# durtest3.net
KiCad netlist of a schematic drawn in EAGLE
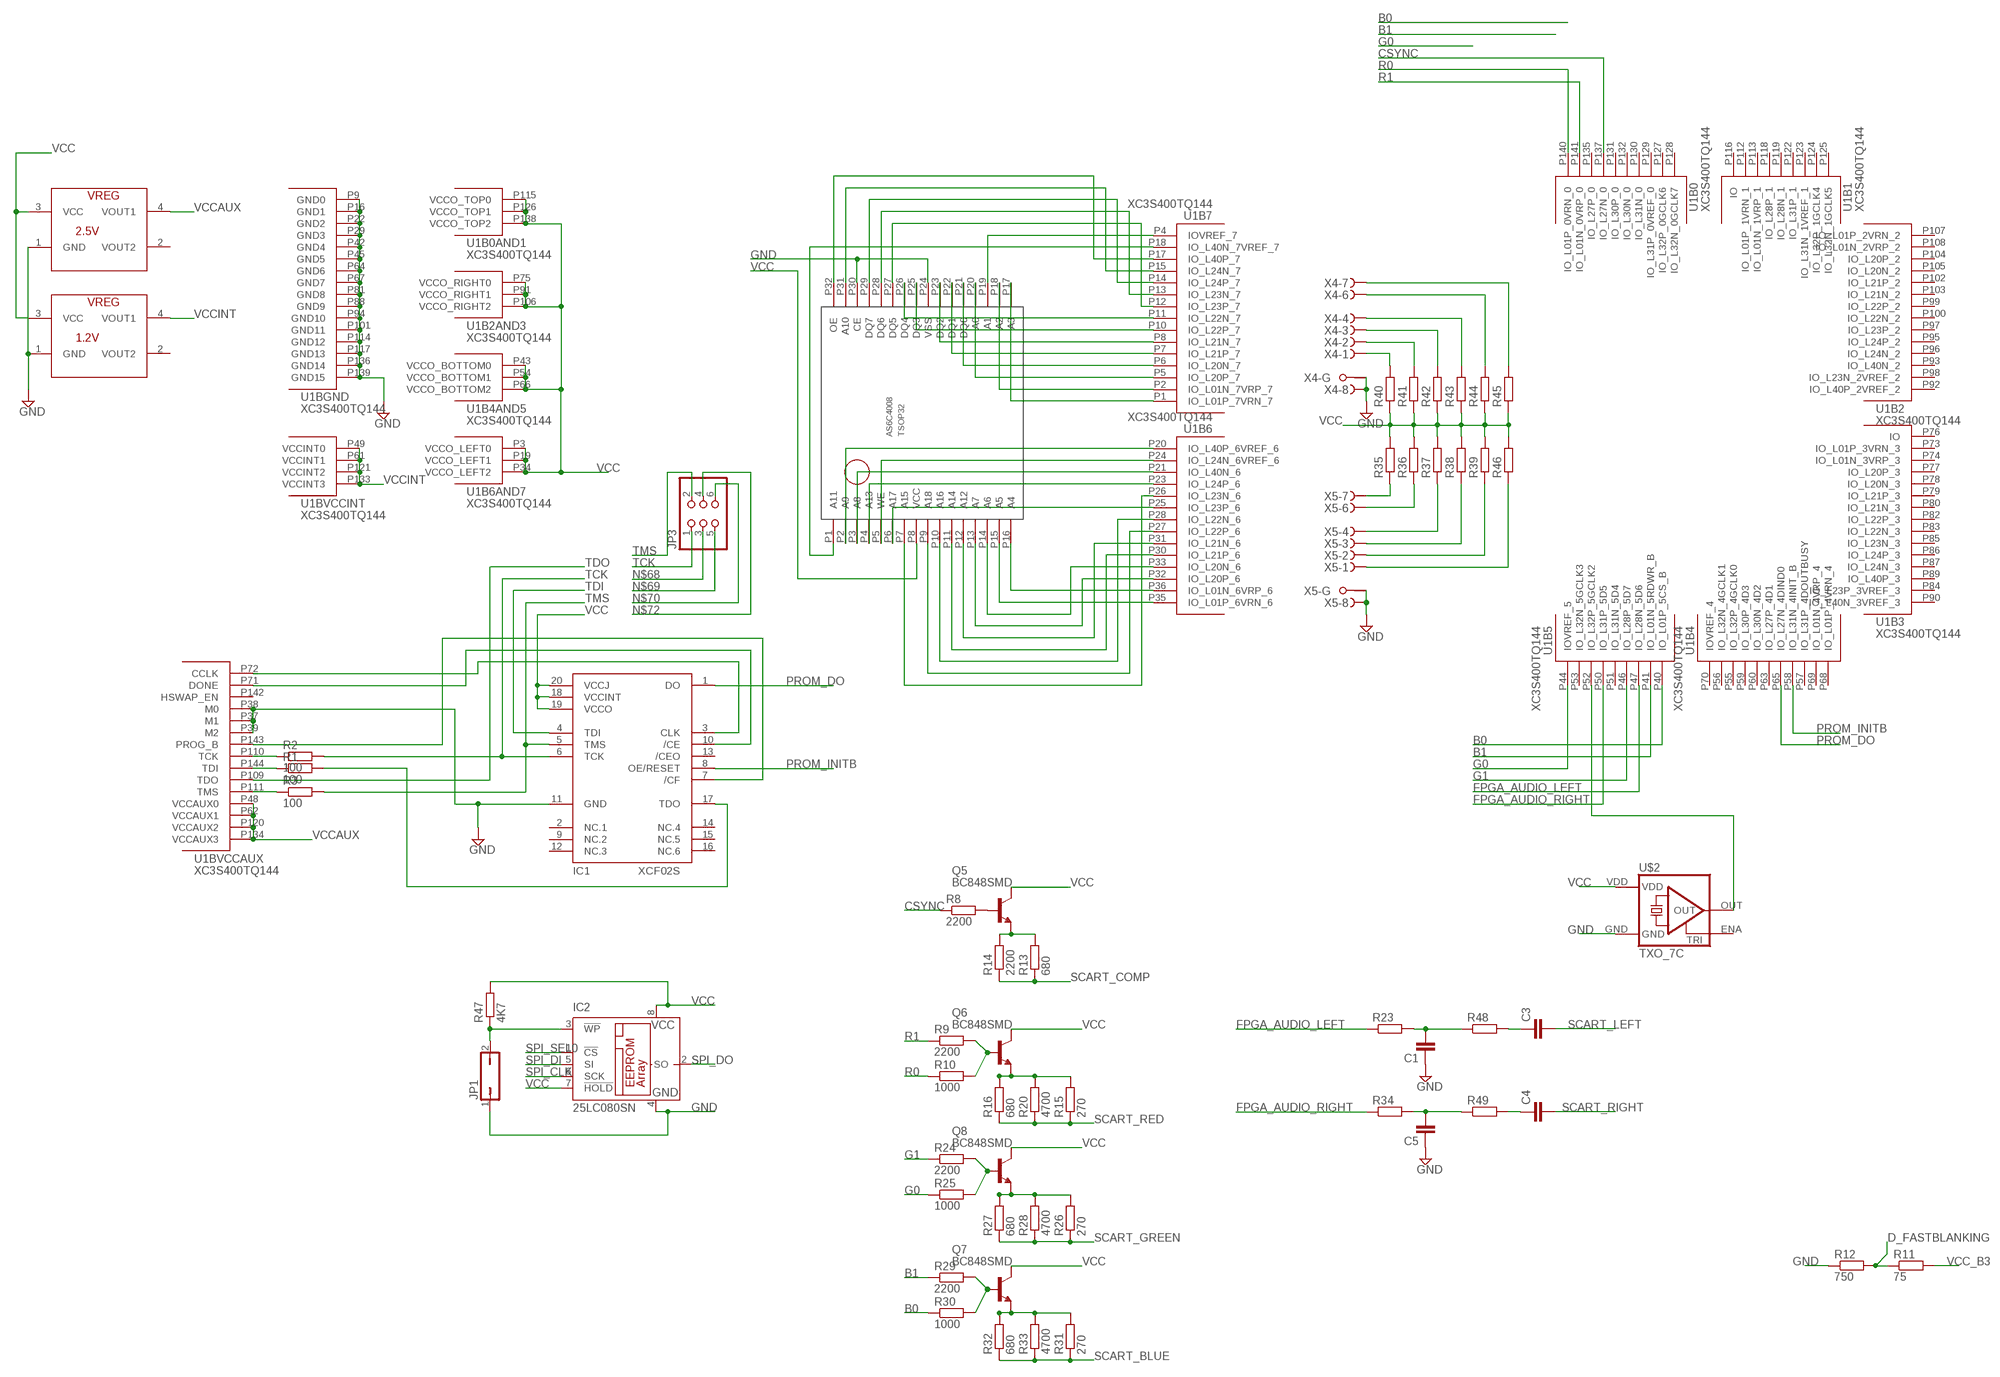
[diagram p0: schematic, sheet 1, part 1 of 2]
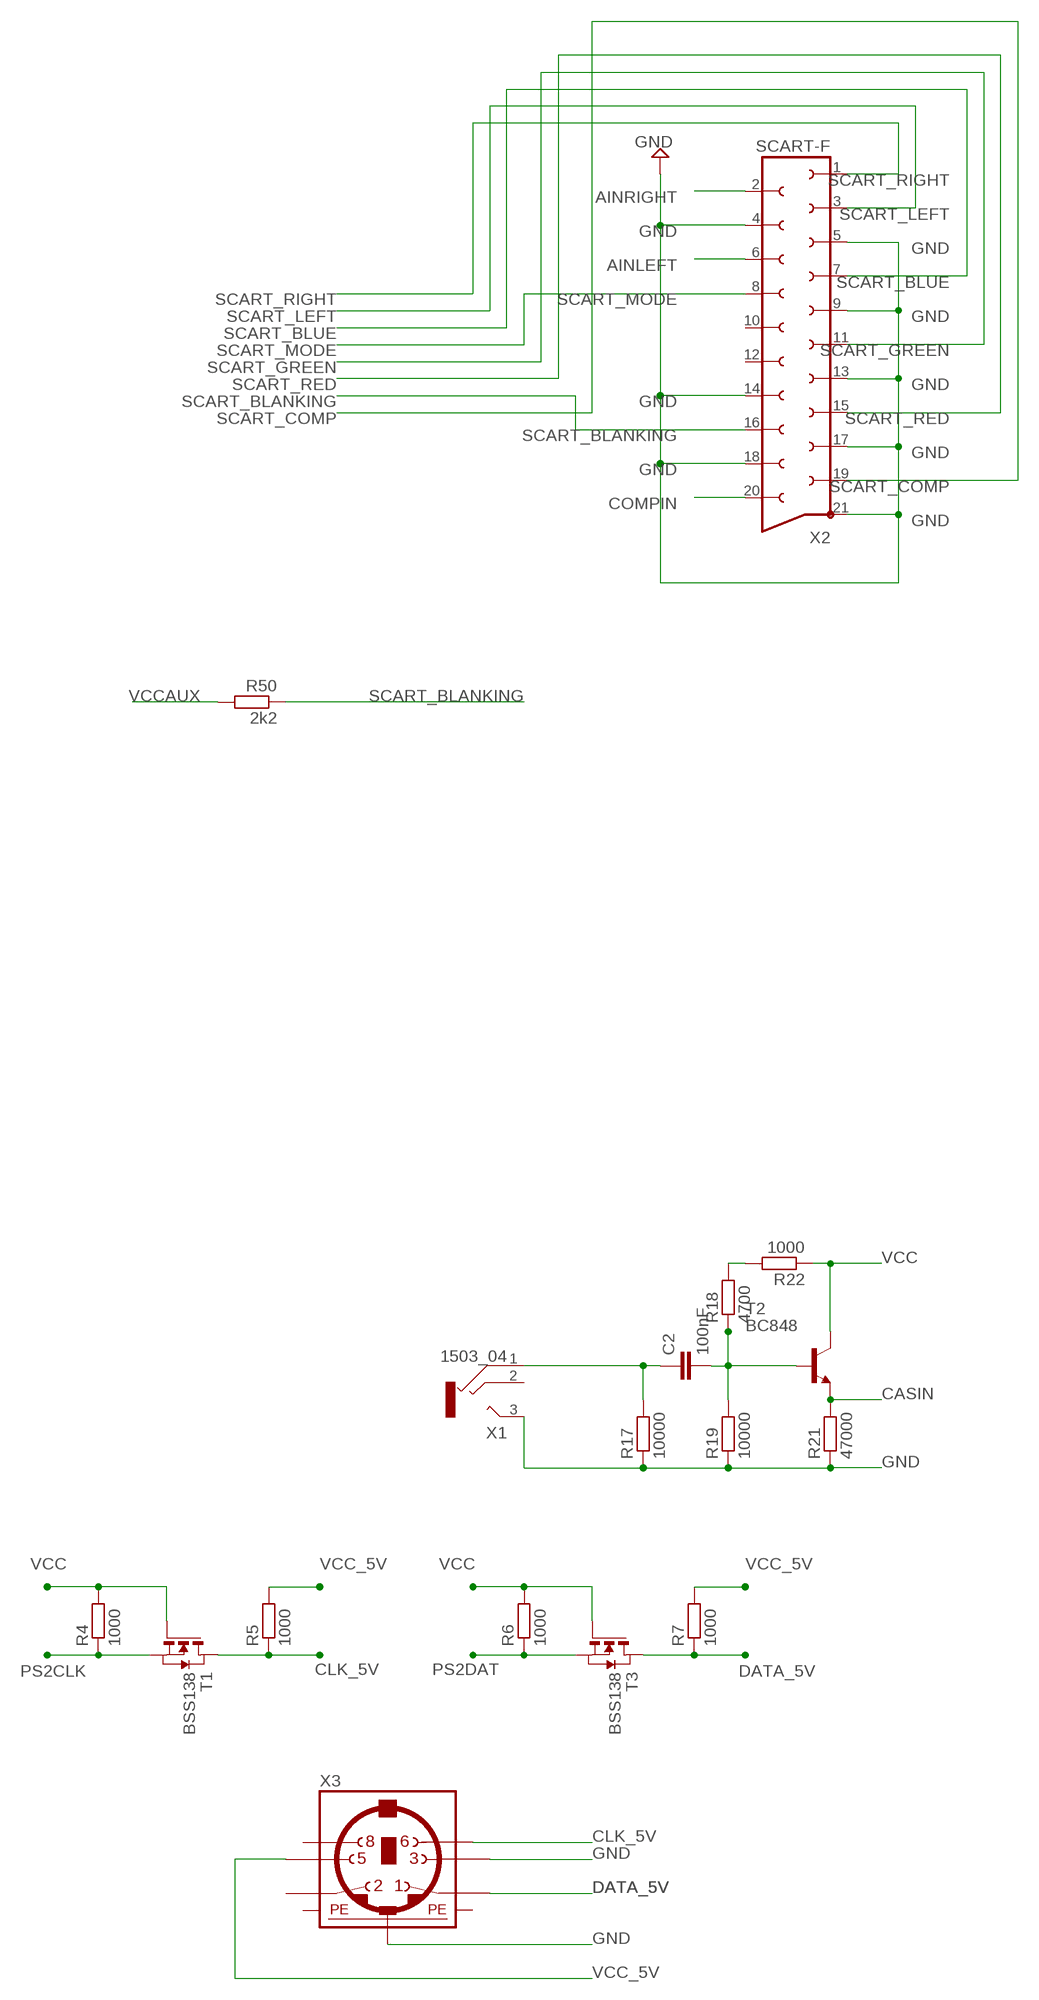
[diagram p1: schematic, sheet 1, part 2 of 2]

(export (version "E")
  (design (tool "Eeschema 10.0.6"))
  (components
    (comp (ref "C1")
      (value "C-EUC0603")
      (footprint "eagle-import:C0603")
      (libsource (lib "eagle-import") (part "C-EUC0603"))
    )
    (comp (ref "C2")
      (value "100nF")
      (footprint "eagle-import:C0603")
      (libsource (lib "eagle-import") (part "C-EUC0603"))
    )
    (comp (ref "C3")
      (value "C-EUC0603")
      (footprint "eagle-import:C0603")
      (libsource (lib "eagle-import") (part "C-EUC0603"))
    )
    (comp (ref "C4")
      (value "C-EUC0603")
      (footprint "eagle-import:C0603")
      (libsource (lib "eagle-import") (part "C-EUC0603"))
    )
    (comp (ref "C5")
      (value "C-EUC0603")
      (footprint "eagle-import:C0603")
      (libsource (lib "eagle-import") (part "C-EUC0603"))
    )
    (comp (ref "IC1")
      (value "XCF02S")
      (footprint "eagle-import:VO20")
      (libsource (lib "eagle-import") (part "XCF02S"))
    )
    (comp (ref "IC2")
      (value "25LC080SN")
      (footprint "eagle-import:SO-08")
      (fields (field (name "MF") "MICROCHIP") (field (name "MPN") "25LC080/SN"))
      (libsource (lib "eagle-import") (part "25SNLC080"))
    )
    (comp (ref "JP1")
      (value "JP1Q")
      (footprint "eagle-import:JP1")
      (libsource (lib "eagle-import") (part "JP1Q"))
    )
    (comp (ref "JP3")
      (value "PINHD-2X3")
      (footprint "eagle-import:2X03")
      (libsource (lib "eagle-import") (part "PINHD-2X3"))
    )
    (comp (ref "Q5")
      (value "BC848SMD")
      (footprint "eagle-import:SOT23")
      (libsource (lib "eagle-import") (part "BC848SMD"))
    )
    (comp (ref "Q6")
      (value "BC848SMD")
      (footprint "eagle-import:SOT23")
      (libsource (lib "eagle-import") (part "BC848SMD"))
    )
    (comp (ref "Q7")
      (value "BC848SMD")
      (footprint "eagle-import:SOT23")
      (libsource (lib "eagle-import") (part "BC848SMD"))
    )
    (comp (ref "Q8")
      (value "BC848SMD")
      (footprint "eagle-import:SOT23")
      (libsource (lib "eagle-import") (part "BC848SMD"))
    )
    (comp (ref "R1")
      (value "100")
      (footprint "eagle-import:R0805")
      (libsource (lib "eagle-import") (part "R-EU_R0805"))
    )
    (comp (ref "R2")
      (value "100")
      (footprint "eagle-import:R0805")
      (libsource (lib "eagle-import") (part "R-EU_R0805"))
    )
    (comp (ref "R3")
      (value "100")
      (footprint "eagle-import:R0805")
      (libsource (lib "eagle-import") (part "R-EU_R0805"))
    )
    (comp (ref "R4")
      (value "1000")
      (footprint "eagle-import:R0805")
      (libsource (lib "eagle-import") (part "R-EU_R0805"))
    )
    (comp (ref "R5")
      (value "1000")
      (footprint "eagle-import:R0805")
      (libsource (lib "eagle-import") (part "R-EU_R0805"))
    )
    (comp (ref "R6")
      (value "1000")
      (footprint "eagle-import:R0805")
      (libsource (lib "eagle-import") (part "R-EU_R0805"))
    )
    (comp (ref "R7")
      (value "1000")
      (footprint "eagle-import:R0805")
      (libsource (lib "eagle-import") (part "R-EU_R0805"))
    )
    (comp (ref "R8")
      (value "2200")
      (footprint "eagle-import:R0805")
      (libsource (lib "eagle-import") (part "R-EU_R0805"))
    )
    (comp (ref "R9")
      (value "2200")
      (footprint "eagle-import:R0805")
      (libsource (lib "eagle-import") (part "R-EU_R0805"))
    )
    (comp (ref "R10")
      (value "1000")
      (footprint "eagle-import:R0805")
      (libsource (lib "eagle-import") (part "R-EU_R0805"))
    )
    (comp (ref "R11")
      (value "75")
      (footprint "eagle-import:R0805")
      (libsource (lib "eagle-import") (part "R-EU_R0805"))
    )
    (comp (ref "R12")
      (value "750")
      (footprint "eagle-import:R0805")
      (libsource (lib "eagle-import") (part "R-EU_R0805"))
    )
    (comp (ref "R13")
      (value "680")
      (footprint "eagle-import:R0805")
      (libsource (lib "eagle-import") (part "R-EU_R0805"))
    )
    (comp (ref "R14")
      (value "2200")
      (footprint "eagle-import:R0805")
      (libsource (lib "eagle-import") (part "R-EU_R0805"))
    )
    (comp (ref "R15")
      (value "270")
      (footprint "eagle-import:R0805")
      (libsource (lib "eagle-import") (part "R-EU_R0805"))
    )
    (comp (ref "R16")
      (value "680")
      (footprint "eagle-import:R0805")
      (libsource (lib "eagle-import") (part "R-EU_R0805"))
    )
    (comp (ref "R17")
      (value "10000")
      (footprint "eagle-import:R0805")
      (libsource (lib "eagle-import") (part "R-EU_R0805"))
    )
    (comp (ref "R18")
      (value "4700")
      (footprint "eagle-import:R0805")
      (libsource (lib "eagle-import") (part "R-EU_R0805"))
    )
    (comp (ref "R19")
      (value "10000")
      (footprint "eagle-import:R0805")
      (libsource (lib "eagle-import") (part "R-EU_R0805"))
    )
    (comp (ref "R20")
      (value "4700")
      (footprint "eagle-import:R0805")
      (libsource (lib "eagle-import") (part "R-EU_R0805"))
    )
    (comp (ref "R21")
      (value "47000")
      (footprint "eagle-import:R0805")
      (libsource (lib "eagle-import") (part "R-EU_R0805"))
    )
    (comp (ref "R22")
      (value "1000")
      (footprint "eagle-import:R0805")
      (libsource (lib "eagle-import") (part "R-EU_R0805"))
    )
    (comp (ref "R23")
      (value "R-EU_M0805")
      (footprint "eagle-import:M0805")
      (libsource (lib "eagle-import") (part "resistor_R-EU_M0805"))
    )
    (comp (ref "R24")
      (value "2200")
      (footprint "eagle-import:R0805")
      (libsource (lib "eagle-import") (part "R-EU_R0805"))
    )
    (comp (ref "R25")
      (value "1000")
      (footprint "eagle-import:R0805")
      (libsource (lib "eagle-import") (part "R-EU_R0805"))
    )
    (comp (ref "R26")
      (value "270")
      (footprint "eagle-import:R0805")
      (libsource (lib "eagle-import") (part "R-EU_R0805"))
    )
    (comp (ref "R27")
      (value "680")
      (footprint "eagle-import:R0805")
      (libsource (lib "eagle-import") (part "R-EU_R0805"))
    )
    (comp (ref "R28")
      (value "4700")
      (footprint "eagle-import:R0805")
      (libsource (lib "eagle-import") (part "R-EU_R0805"))
    )
    (comp (ref "R29")
      (value "2200")
      (footprint "eagle-import:R0805")
      (libsource (lib "eagle-import") (part "R-EU_R0805"))
    )
    (comp (ref "R30")
      (value "1000")
      (footprint "eagle-import:R0805")
      (libsource (lib "eagle-import") (part "R-EU_R0805"))
    )
    (comp (ref "R31")
      (value "270")
      (footprint "eagle-import:R0805")
      (libsource (lib "eagle-import") (part "R-EU_R0805"))
    )
    (comp (ref "R32")
      (value "680")
      (footprint "eagle-import:R0805")
      (libsource (lib "eagle-import") (part "R-EU_R0805"))
    )
    (comp (ref "R33")
      (value "4700")
      (footprint "eagle-import:R0805")
      (libsource (lib "eagle-import") (part "R-EU_R0805"))
    )
    (comp (ref "R34")
      (value "R-EU_M0805")
      (footprint "eagle-import:M0805")
      (libsource (lib "eagle-import") (part "resistor_R-EU_M0805"))
    )
    (comp (ref "R35")
      (value "R-EU_M0805")
      (footprint "eagle-import:M0805")
      (libsource (lib "eagle-import") (part "resistor_R-EU_M0805"))
    )
    (comp (ref "R36")
      (value "R-EU_M0805")
      (footprint "eagle-import:M0805")
      (libsource (lib "eagle-import") (part "resistor_R-EU_M0805"))
    )
    (comp (ref "R37")
      (value "R-EU_M0805")
      (footprint "eagle-import:M0805")
      (libsource (lib "eagle-import") (part "resistor_R-EU_M0805"))
    )
    (comp (ref "R38")
      (value "R-EU_M0805")
      (footprint "eagle-import:M0805")
      (libsource (lib "eagle-import") (part "resistor_R-EU_M0805"))
    )
    (comp (ref "R39")
      (value "R-EU_M0805")
      (footprint "eagle-import:M0805")
      (libsource (lib "eagle-import") (part "resistor_R-EU_M0805"))
    )
    (comp (ref "R40")
      (value "R-EU_M0805")
      (footprint "eagle-import:M0805")
      (libsource (lib "eagle-import") (part "resistor_R-EU_M0805"))
    )
    (comp (ref "R41")
      (value "R-EU_M0805")
      (footprint "eagle-import:M0805")
      (libsource (lib "eagle-import") (part "resistor_R-EU_M0805"))
    )
    (comp (ref "R42")
      (value "R-EU_M0805")
      (footprint "eagle-import:M0805")
      (libsource (lib "eagle-import") (part "resistor_R-EU_M0805"))
    )
    (comp (ref "R43")
      (value "R-EU_M0805")
      (footprint "eagle-import:M0805")
      (libsource (lib "eagle-import") (part "resistor_R-EU_M0805"))
    )
    (comp (ref "R44")
      (value "R-EU_M0805")
      (footprint "eagle-import:M0805")
      (libsource (lib "eagle-import") (part "resistor_R-EU_M0805"))
    )
    (comp (ref "R45")
      (value "R-EU_M0805")
      (footprint "eagle-import:M0805")
      (libsource (lib "eagle-import") (part "resistor_R-EU_M0805"))
    )
    (comp (ref "R46")
      (value "R-EU_M0805")
      (footprint "eagle-import:M0805")
      (libsource (lib "eagle-import") (part "resistor_R-EU_M0805"))
    )
    (comp (ref "R47")
      (value "4K7")
      (footprint "eagle-import:R0805")
      (libsource (lib "eagle-import") (part "R-EU_R0805"))
    )
    (comp (ref "R48")
      (value "R-EU_M0805")
      (footprint "eagle-import:M0805")
      (libsource (lib "eagle-import") (part "resistor_R-EU_M0805"))
    )
    (comp (ref "R49")
      (value "R-EU_M0805")
      (footprint "eagle-import:M0805")
      (libsource (lib "eagle-import") (part "resistor_R-EU_M0805"))
    )
    (comp (ref "R50")
      (value "2k2")
      (footprint "eagle-import:M0805")
      (libsource (lib "eagle-import") (part "resistor_R-EU_M0805"))
    )
    (comp (ref "REG1.2")
      (value "1.2V")
      (footprint "eagle-import:SOT223")
      (libsource (lib "eagle-import") (part "NX1117"))
    )
    (comp (ref "REG2.5")
      (value "2.5V")
      (footprint "eagle-import:SOT223")
      (libsource (lib "eagle-import") (part "NX1117"))
    )
    (comp (ref "T1")
      (value "BSS138")
      (footprint "eagle-import:SOT-23")
      (libsource (lib "eagle-import") (part "NMOSSOT23"))
    )
    (comp (ref "T2")
      (value "BC848")
      (footprint "eagle-import:SOT23")
      (libsource (lib "eagle-import") (part "BC848"))
    )
    (comp (ref "T3")
      (value "BSS138")
      (footprint "eagle-import:SOT-23")
      (libsource (lib "eagle-import") (part "NMOSSOT23"))
    )
    (comp (ref "U$1")
      (value "AS6C4008")
      (footprint "eagle-import:TSOP32")
      (libsource (lib "eagle-import") (part "AS6C4008"))
    )
    (comp (ref "U$2")
      (value "TXO_7C")
      (footprint "eagle-import:OSC_7C")
      (libsource (lib "eagle-import") (part "TXO_7C"))
    )
    (comp (ref "U1")
      (value "XC3S400TQ144")
      (footprint "eagle-import:TQ144")
      (libsource (lib "eagle-import") (part "XC3S400TQ144"))
    )
    (comp (ref "X1")
      (value "1503_04")
      (footprint "eagle-import:1503_04")
      (libsource (lib "eagle-import") (part "1503_04"))
    )
    (comp (ref "X2")
      (value "SCART-F")
      (footprint "eagle-import:SCART-F")
      (libsource (lib "eagle-import") (part "SCART-F"))
    )
    (comp (ref "X3")
      (value "MINI_DIN_6")
      (footprint "eagle-import:M_DIN6")
      (libsource (lib "eagle-import") (part "MINI_DIN_6"))
    )
    (comp (ref "X4")
      (value "F09HPS")
      (footprint "eagle-import:F09HP")
      (libsource (lib "eagle-import") (part "F09HPS"))
    )
    (comp (ref "X5")
      (value "F09HPS")
      (footprint "eagle-import:F09HP")
      (libsource (lib "eagle-import") (part "F09HPS"))
    )
  )
  (nets
    (net (code "1") (name "/AINLEFT") (class "Default")
      (node (ref "X2") (pin "6") (pinfunction "6_6") (pintype "passive"))
    )
    (net (code "2") (name "/AINRIGHT") (class "Default")
      (node (ref "X2") (pin "2") (pinfunction "2_2") (pintype "passive"))
    )
    (net (code "3") (name "/B0") (class "Default")
      (node (ref "R30") (pin "1") (pinfunction "1_1") (pintype "passive"))
      (node (ref "U1") (pin "P40") (pinfunction "IO_L01P_5CS_B_P40") (pintype "bidirectional"))
    )
    (net (code "4") (name "/B1") (class "Default")
      (node (ref "R29") (pin "1") (pinfunction "1_1") (pintype "passive"))
      (node (ref "U1") (pin "P41") (pinfunction "IO_L01N_5RDWR_B_P41") (pintype "bidirectional"))
    )
    (net (code "5") (name "/CASIN") (class "Default")
      (node (ref "R21") (pin "2") (pinfunction "2_2") (pintype "passive"))
      (node (ref "T2") (pin "2") (pinfunction "E_2") (pintype "passive"))
    )
    (net (code "6") (name "/CLK_5V") (class "Default")
      (node (ref "R5") (pin "1") (pinfunction "1_1") (pintype "passive"))
      (node (ref "T1") (pin "1") (pinfunction "D_1") (pintype "passive"))
      (node (ref "X3") (pin "6") (pinfunction "6_6") (pintype "passive"))
    )
    (net (code "7") (name "/COMPIN") (class "Default")
      (node (ref "X2") (pin "20") (pinfunction "20_20") (pintype "passive"))
    )
    (net (code "8") (name "/CSYNC") (class "Default")
      (node (ref "R8") (pin "1") (pinfunction "1_1") (pintype "passive"))
      (node (ref "U1") (pin "P137") (pinfunction "IO_L27N_0_P137") (pintype "bidirectional"))
    )
    (net (code "9") (name "/DATA_5V") (class "Default")
      (node (ref "R7") (pin "1") (pinfunction "1_1") (pintype "passive"))
      (node (ref "T3") (pin "1") (pinfunction "D_1") (pintype "passive"))
      (node (ref "X3") (pin "1") (pinfunction "1_1") (pintype "passive"))
    )
    (net (code "10") (name "/D_FASTBLANKING") (class "Default")
      (node (ref "R11") (pin "1") (pinfunction "1_1") (pintype "passive"))
      (node (ref "R12") (pin "2") (pinfunction "2_2") (pintype "passive"))
    )
    (net (code "11") (name "/FPGA_AUDIO_LEFT") (class "Default")
      (node (ref "R23") (pin "1") (pinfunction "1_1") (pintype "passive"))
      (node (ref "U1") (pin "P47") (pinfunction "IO_L28N_5D6_P47") (pintype "bidirectional"))
    )
    (net (code "12") (name "/FPGA_AUDIO_RIGHT") (class "Default")
      (node (ref "R34") (pin "1") (pinfunction "1_1") (pintype "passive"))
      (node (ref "U1") (pin "P50") (pinfunction "IO_L31P_5D5_P50") (pintype "bidirectional"))
    )
    (net (code "13") (name "/G0") (class "Default")
      (node (ref "R25") (pin "1") (pinfunction "1_1") (pintype "passive"))
      (node (ref "U1") (pin "P44") (pinfunction "IOVREF_5_P44") (pintype "bidirectional"))
    )
    (net (code "14") (name "/G1") (class "Default")
      (node (ref "R24") (pin "1") (pinfunction "1_1") (pintype "passive"))
      (node (ref "U1") (pin "P46") (pinfunction "IO_L28P_5D7_P46") (pintype "bidirectional"))
    )
    (net (code "15") (name "/N$68") (class "Default")
      (node (ref "JP3") (pin "3") (pinfunction "3_3") (pintype "passive"))
    )
    (net (code "16") (name "/N$69") (class "Default")
      (node (ref "JP3") (pin "5") (pinfunction "5_5") (pintype "passive"))
    )
    (net (code "17") (name "/N$70") (class "Default")
      (node (ref "JP3") (pin "6") (pinfunction "6_6") (pintype "passive"))
    )
    (net (code "18") (name "/N$72") (class "Default")
      (node (ref "JP3") (pin "4") (pinfunction "4_4") (pintype "passive"))
    )
    (net (code "19") (name "/PE1") (class "Default")
      (node (ref "X3") (pin "SH1") (pinfunction "PE1_SH1") (pintype "power_in"))
    )
    (net (code "20") (name "/PE3") (class "Default")
      (node (ref "X3") (pin "SH3") (pinfunction "PE3_SH3") (pintype "power_in"))
    )
    (net (code "21") (name "/PROM_DO") (class "Default")
      (node (ref "IC1") (pin "1") (pinfunction "DO_1") (pintype "bidirectional"))
      (node (ref "U1") (pin "P65") (pinfunction "IO_L27N_4DIND0_P65") (pintype "bidirectional"))
    )
    (net (code "22") (name "/PROM_INITB") (class "Default")
      (node (ref "IC1") (pin "8") (pinfunction "OE/RESET_8") (pintype "bidirectional"))
      (node (ref "U1") (pin "P58") (pinfunction "IO_L31N_4INIT_B_P58") (pintype "bidirectional"))
    )
    (net (code "23") (name "/PS2CLK") (class "Default")
      (node (ref "R4") (pin "1") (pinfunction "1_1") (pintype "passive"))
      (node (ref "T1") (pin "2") (pinfunction "S_2") (pintype "passive"))
    )
    (net (code "24") (name "/PS2DAT") (class "Default")
      (node (ref "R6") (pin "1") (pinfunction "1_1") (pintype "passive"))
      (node (ref "T3") (pin "2") (pinfunction "S_2") (pintype "passive"))
    )
    (net (code "25") (name "/R0") (class "Default")
      (node (ref "R10") (pin "1") (pinfunction "1_1") (pintype "passive"))
      (node (ref "U1") (pin "P140") (pinfunction "IO_L01P_0VRN_0_P140") (pintype "bidirectional"))
    )
    (net (code "26") (name "/R1") (class "Default")
      (node (ref "R9") (pin "1") (pinfunction "1_1") (pintype "passive"))
      (node (ref "U1") (pin "P141") (pinfunction "IO_L01N_0VRP_0_P141") (pintype "bidirectional"))
    )
    (net (code "27") (name "/SCART_BLANKING") (class "Default")
      (node (ref "R50") (pin "1") (pinfunction "1_1") (pintype "passive"))
      (node (ref "X2") (pin "16") (pinfunction "16_16") (pintype "passive"))
    )
    (net (code "28") (name "/SCART_BLUE") (class "Default")
      (node (ref "R31") (pin "1") (pinfunction "1_1") (pintype "passive"))
      (node (ref "R32") (pin "1") (pinfunction "1_1") (pintype "passive"))
      (node (ref "R33") (pin "1") (pinfunction "1_1") (pintype "passive"))
      (node (ref "X2") (pin "7") (pinfunction "7_7") (pintype "passive"))
    )
    (net (code "29") (name "/SCART_COMP") (class "Default")
      (node (ref "R13") (pin "1") (pinfunction "1_1") (pintype "passive"))
      (node (ref "R14") (pin "1") (pinfunction "1_1") (pintype "passive"))
      (node (ref "X2") (pin "19") (pinfunction "19_19") (pintype "passive"))
    )
    (net (code "30") (name "/SCART_GREEN") (class "Default")
      (node (ref "R26") (pin "1") (pinfunction "1_1") (pintype "passive"))
      (node (ref "R27") (pin "1") (pinfunction "1_1") (pintype "passive"))
      (node (ref "R28") (pin "1") (pinfunction "1_1") (pintype "passive"))
      (node (ref "X2") (pin "11") (pinfunction "11_11") (pintype "passive"))
    )
    (net (code "31") (name "/SCART_LEFT") (class "Default")
      (node (ref "C3") (pin "2") (pinfunction "2_2") (pintype "passive"))
      (node (ref "X2") (pin "3") (pinfunction "3_3") (pintype "passive"))
    )
    (net (code "32") (name "/SCART_MODE") (class "Default")
      (node (ref "X2") (pin "8") (pinfunction "8_8") (pintype "passive"))
    )
    (net (code "33") (name "/SCART_RED") (class "Default")
      (node (ref "R15") (pin "1") (pinfunction "1_1") (pintype "passive"))
      (node (ref "R16") (pin "1") (pinfunction "1_1") (pintype "passive"))
      (node (ref "R20") (pin "1") (pinfunction "1_1") (pintype "passive"))
      (node (ref "X2") (pin "15") (pinfunction "15_15") (pintype "passive"))
    )
    (net (code "34") (name "/SCART_RIGHT") (class "Default")
      (node (ref "C4") (pin "2") (pinfunction "2_2") (pintype "passive"))
      (node (ref "X2") (pin "1") (pinfunction "1_1") (pintype "passive"))
    )
    (net (code "35") (name "/SPI_CLK") (class "Default")
      (node (ref "IC2") (pin "6") (pinfunction "SCK_6") (pintype "input"))
    )
    (net (code "36") (name "/SPI_DI") (class "Default")
      (node (ref "IC2") (pin "5") (pinfunction "SI_5") (pintype "input"))
    )
    (net (code "37") (name "/SPI_DO") (class "Default")
      (node (ref "IC2") (pin "2") (pinfunction "SO_2") (pintype "bidirectional"))
    )
    (net (code "38") (name "/SPI_SEL0") (class "Default")
      (node (ref "IC2") (pin "1") (pinfunction "~{CS}_1") (pintype "input"))
    )
    (net (code "39") (name "/TCK") (class "Default")
      (node (ref "IC1") (pin "6") (pinfunction "TCK_6") (pintype "bidirectional"))
      (node (ref "JP3") (pin "1") (pinfunction "1_1") (pintype "passive"))
      (node (ref "R2") (pin "2") (pinfunction "2_2") (pintype "passive"))
    )
    (net (code "40") (name "/TDI") (class "Default")
      (node (ref "IC1") (pin "4") (pinfunction "TDI_4") (pintype "bidirectional"))
    )
    (net (code "41") (name "/TDO") (class "Default")
      (node (ref "U1") (pin "P109") (pinfunction "TDO_P109") (pintype "bidirectional"))
    )
    (net (code "42") (name "/TMS") (class "Default")
      (node (ref "IC1") (pin "5") (pinfunction "TMS_5") (pintype "bidirectional"))
      (node (ref "JP3") (pin "2") (pinfunction "2_2") (pintype "passive"))
      (node (ref "R3") (pin "2") (pinfunction "2_2") (pintype "passive"))
    )
    (net (code "43") (name "/VCC") (class "Default")
      (node (ref "IC1") (pin "18") (pinfunction "VCCINT_18") (pintype "bidirectional"))
      (node (ref "IC1") (pin "19") (pinfunction "VCCO_19") (pintype "bidirectional"))
      (node (ref "IC1") (pin "20") (pinfunction "VCCJ_20") (pintype "bidirectional"))
      (node (ref "IC2") (pin "7") (pinfunction "~{HOLD}_7") (pintype "input"))
      (node (ref "IC2") (pin "8") (pinfunction "VCC_8") (pintype "power_in"))
      (node (ref "Q5") (pin "3") (pinfunction "C_3") (pintype "passive"))
      (node (ref "Q6") (pin "3") (pinfunction "C_3") (pintype "passive"))
      (node (ref "Q7") (pin "3") (pinfunction "C_3") (pintype "passive"))
      (node (ref "Q8") (pin "3") (pinfunction "C_3") (pintype "passive"))
      (node (ref "R22") (pin "1") (pinfunction "1_1") (pintype "passive"))
      (node (ref "R35") (pin "2") (pinfunction "2_2") (pintype "passive"))
      (node (ref "R36") (pin "2") (pinfunction "2_2") (pintype "passive"))
      (node (ref "R37") (pin "2") (pinfunction "2_2") (pintype "passive"))
      (node (ref "R38") (pin "2") (pinfunction "2_2") (pintype "passive"))
      (node (ref "R39") (pin "2") (pinfunction "2_2") (pintype "passive"))
      (node (ref "R4") (pin "2") (pinfunction "2_2") (pintype "passive"))
      (node (ref "R40") (pin "1") (pinfunction "1_1") (pintype "passive"))
      (node (ref "R41") (pin "1") (pinfunction "1_1") (pintype "passive"))
      (node (ref "R42") (pin "1") (pinfunction "1_1") (pintype "passive"))
      (node (ref "R43") (pin "1") (pinfunction "1_1") (pintype "passive"))
      (node (ref "R44") (pin "1") (pinfunction "1_1") (pintype "passive"))
      (node (ref "R45") (pin "1") (pinfunction "1_1") (pintype "passive"))
      (node (ref "R46") (pin "2") (pinfunction "2_2") (pintype "passive"))
      (node (ref "R47") (pin "2") (pinfunction "2_2") (pintype "passive"))
      (node (ref "R6") (pin "2") (pinfunction "2_2") (pintype "passive"))
      (node (ref "REG1.2") (pin "3") (pinfunction "VCC_3") (pintype "bidirectional"))
      (node (ref "REG2.5") (pin "3") (pinfunction "VCC_3") (pintype "bidirectional"))
      (node (ref "T1") (pin "3") (pinfunction "G_3") (pintype "passive"))
      (node (ref "T2") (pin "3") (pinfunction "C_3") (pintype "passive"))
      (node (ref "T3") (pin "3") (pinfunction "G_3") (pintype "passive"))
      (node (ref "U$1") (pin "P8") (pinfunction "VCC_P8") (pintype "bidirectional"))
      (node (ref "U$2") (pin "VDD") (pinfunction "VDD_VDD") (pintype "power_in"))
      (node (ref "U1") (pin "P106") (pinfunction "VCCO_RIGHT2_P106") (pintype "passive"))
      (node (ref "U1") (pin "P115") (pinfunction "VCCO_TOP0_P115") (pintype "passive"))
      (node (ref "U1") (pin "P126") (pinfunction "VCCO_TOP1_P126") (pintype "passive"))
      (node (ref "U1") (pin "P138") (pinfunction "VCCO_TOP2_P138") (pintype "passive"))
      (node (ref "U1") (pin "P19") (pinfunction "VCCO_LEFT1_P19") (pintype "passive"))
      (node (ref "U1") (pin "P3") (pinfunction "VCCO_LEFT0_P3") (pintype "passive"))
      (node (ref "U1") (pin "P34") (pinfunction "VCCO_LEFT2_P34") (pintype "passive"))
      (node (ref "U1") (pin "P43") (pinfunction "VCCO_BOTTOM0_P43") (pintype "passive"))
      (node (ref "U1") (pin "P54") (pinfunction "VCCO_BOTTOM1_P54") (pintype "passive"))
      (node (ref "U1") (pin "P66") (pinfunction "VCCO_BOTTOM2_P66") (pintype "passive"))
      (node (ref "U1") (pin "P75") (pinfunction "VCCO_RIGHT0_P75") (pintype "passive"))
      (node (ref "U1") (pin "P91") (pinfunction "VCCO_RIGHT1_P91") (pintype "passive"))
    )
    (net (code "44") (name "/VCCAUX") (class "Default")
      (node (ref "R50") (pin "2") (pinfunction "2_2") (pintype "passive"))
      (node (ref "REG2.5") (pin "4") (pinfunction "VOUT1_4") (pintype "bidirectional"))
      (node (ref "U1") (pin "P120") (pinfunction "VCCAUX2_P120") (pintype "passive"))
      (node (ref "U1") (pin "P134") (pinfunction "VCCAUX3_P134") (pintype "passive"))
      (node (ref "U1") (pin "P48") (pinfunction "VCCAUX0_P48") (pintype "passive"))
      (node (ref "U1") (pin "P62") (pinfunction "VCCAUX1_P62") (pintype "passive"))
    )
    (net (code "45") (name "/VCCINT") (class "Default")
      (node (ref "REG1.2") (pin "4") (pinfunction "VOUT1_4") (pintype "bidirectional"))
      (node (ref "U1") (pin "P121") (pinfunction "VCCINT2_P121") (pintype "passive"))
      (node (ref "U1") (pin "P133") (pinfunction "VCCINT3_P133") (pintype "passive"))
      (node (ref "U1") (pin "P49") (pinfunction "VCCINT0_P49") (pintype "passive"))
      (node (ref "U1") (pin "P61") (pinfunction "VCCINT1_P61") (pintype "passive"))
    )
    (net (code "46") (name "/VCC_5V") (class "Default")
      (node (ref "R5") (pin "2") (pinfunction "2_2") (pintype "passive"))
      (node (ref "R7") (pin "2") (pinfunction "2_2") (pintype "passive"))
      (node (ref "X3") (pin "5") (pinfunction "5_5") (pintype "passive"))
    )
    (net (code "47") (name "/VCC_B3") (class "Default")
      (node (ref "R11") (pin "2") (pinfunction "2_2") (pintype "passive"))
    )
    (net (code "48") (name "GND") (class "Default")
      (node (ref "C1") (pin "1") (pinfunction "1_1") (pintype "passive"))
      (node (ref "C5") (pin "1") (pinfunction "1_1") (pintype "passive"))
      (node (ref "IC1") (pin "11") (pinfunction "GND_11") (pintype "bidirectional"))
      (node (ref "IC2") (pin "4") (pinfunction "GND_4") (pintype "power_in"))
      (node (ref "JP1") (pin "1") (pinfunction "1_1") (pintype "passive"))
      (node (ref "R12") (pin "1") (pinfunction "1_1") (pintype "passive"))
      (node (ref "R17") (pin "1") (pinfunction "1_1") (pintype "passive"))
      (node (ref "R19") (pin "1") (pinfunction "1_1") (pintype "passive"))
      (node (ref "R21") (pin "1") (pinfunction "1_1") (pintype "passive"))
      (node (ref "REG1.2") (pin "1") (pinfunction "GND_1") (pintype "bidirectional"))
      (node (ref "REG2.5") (pin "1") (pinfunction "GND_1") (pintype "bidirectional"))
      (node (ref "U$1") (pin "P24") (pinfunction "VSS_P24") (pintype "bidirectional"))
      (node (ref "U$1") (pin "P30") (pinfunction "CE_P30") (pintype "bidirectional"))
      (node (ref "U$2") (pin "GND") (pinfunction "GND_GND") (pintype "power_in"))
      (node (ref "U1") (pin "P101") (pinfunction "GND11_P101") (pintype "passive"))
      (node (ref "U1") (pin "P114") (pinfunction "GND12_P114") (pintype "passive"))
      (node (ref "U1") (pin "P117") (pinfunction "GND13_P117") (pintype "passive"))
      (node (ref "U1") (pin "P136") (pinfunction "GND14_P136") (pintype "passive"))
      (node (ref "U1") (pin "P139") (pinfunction "GND15_P139") (pintype "passive"))
      (node (ref "U1") (pin "P16") (pinfunction "GND1_P16") (pintype "passive"))
      (node (ref "U1") (pin "P22") (pinfunction "GND2_P22") (pintype "passive"))
      (node (ref "U1") (pin "P29") (pinfunction "GND3_P29") (pintype "passive"))
      (node (ref "U1") (pin "P37") (pinfunction "M1_P37") (pintype "bidirectional"))
      (node (ref "U1") (pin "P38") (pinfunction "M0_P38") (pintype "bidirectional"))
      (node (ref "U1") (pin "P39") (pinfunction "M2_P39") (pintype "bidirectional"))
      (node (ref "U1") (pin "P42") (pinfunction "GND4_P42") (pintype "passive"))
      (node (ref "U1") (pin "P45") (pinfunction "GND5_P45") (pintype "passive"))
      (node (ref "U1") (pin "P64") (pinfunction "GND6_P64") (pintype "passive"))
      (node (ref "U1") (pin "P67") (pinfunction "GND7_P67") (pintype "passive"))
      (node (ref "U1") (pin "P81") (pinfunction "GND8_P81") (pintype "passive"))
      (node (ref "U1") (pin "P88") (pinfunction "GND9_P88") (pintype "passive"))
      (node (ref "U1") (pin "P9") (pinfunction "GND0_P9") (pintype "passive"))
      (node (ref "U1") (pin "P94") (pinfunction "GND10_P94") (pintype "passive"))
      (node (ref "X1") (pin "3") (pinfunction "2_3") (pintype "passive"))
      (node (ref "X2") (pin "13") (pinfunction "13_13") (pintype "passive"))
      (node (ref "X2") (pin "14") (pinfunction "14_14") (pintype "passive"))
      (node (ref "X2") (pin "17") (pinfunction "17_17") (pintype "passive"))
      (node (ref "X2") (pin "18") (pinfunction "18_18") (pintype "passive"))
      (node (ref "X2") (pin "21") (pinfunction "21_21") (pintype "passive"))
      (node (ref "X2") (pin "4") (pinfunction "4_4") (pintype "passive"))
      (node (ref "X2") (pin "5") (pinfunction "5_5") (pintype "passive"))
      (node (ref "X2") (pin "9") (pinfunction "9_9") (pintype "passive"))
      (node (ref "X3") (pin "3") (pinfunction "3_3") (pintype "passive"))
      (node (ref "X3") (pin "SH2") (pinfunction "PE2_SH2") (pintype "power_in"))
      (node (ref "X4") (pin "8") (pinfunction "F_8") (pintype "passive"))
      (node (ref "X4") (pin "G1") (pinfunction "G1_G1") (pintype "passive"))
      (node (ref "X5") (pin "8") (pinfunction "F_8") (pintype "passive"))
      (node (ref "X5") (pin "G1") (pinfunction "G1_G1") (pintype "passive"))
    )
    (net (code "49") (name "Net-(C1-Pad2)") (class "Default")
      (node (ref "C1") (pin "2") (pinfunction "2_2") (pintype "passive"))
      (node (ref "R23") (pin "2") (pinfunction "2_2") (pintype "passive"))
      (node (ref "R48") (pin "1") (pinfunction "1_1") (pintype "passive"))
    )
    (net (code "50") (name "Net-(C2-Pad1)") (class "Default")
      (node (ref "C2") (pin "1") (pinfunction "1_1") (pintype "passive"))
      (node (ref "R17") (pin "2") (pinfunction "2_2") (pintype "passive"))
      (node (ref "X1") (pin "1") (pinfunction "1_1") (pintype "passive"))
    )
    (net (code "51") (name "Net-(C3-Pad1)") (class "Default")
      (node (ref "C3") (pin "1") (pinfunction "1_1") (pintype "passive"))
      (node (ref "R48") (pin "2") (pinfunction "2_2") (pintype "passive"))
    )
    (net (code "52") (name "Net-(C4-Pad1)") (class "Default")
      (node (ref "C4") (pin "1") (pinfunction "1_1") (pintype "passive"))
      (node (ref "R49") (pin "2") (pinfunction "2_2") (pintype "passive"))
    )
    (net (code "53") (name "Net-(C5-Pad2)") (class "Default")
      (node (ref "C5") (pin "2") (pinfunction "2_2") (pintype "passive"))
      (node (ref "R34") (pin "2") (pinfunction "2_2") (pintype "passive"))
      (node (ref "R49") (pin "1") (pinfunction "1_1") (pintype "passive"))
    )
    (net (code "54") (name "Net-(IC1-CLK)") (class "Default")
      (node (ref "IC1") (pin "3") (pinfunction "CLK_3") (pintype "bidirectional"))
      (node (ref "U1") (pin "P72") (pinfunction "CCLK_P72") (pintype "bidirectional"))
    )
    (net (code "55") (name "Net-(IC1-TDO)") (class "Default")
      (node (ref "IC1") (pin "17") (pinfunction "TDO_17") (pintype "bidirectional"))
      (node (ref "R1") (pin "2") (pinfunction "2_2") (pintype "passive"))
    )
    (net (code "56") (name "Net-(IC1-{slash}CE)") (class "Default")
      (node (ref "IC1") (pin "10") (pinfunction "/CE_10") (pintype "bidirectional"))
      (node (ref "U1") (pin "P71") (pinfunction "DONE_P71") (pintype "bidirectional"))
    )
    (net (code "57") (name "Net-(IC1-{slash}CF)") (class "Default")
      (node (ref "IC1") (pin "7") (pinfunction "/CF_7") (pintype "bidirectional"))
      (node (ref "U1") (pin "P143") (pinfunction "PROG_B_P143") (pintype "bidirectional"))
    )
    (net (code "58") (name "Net-(IC2-~{WP})") (class "Default")
      (node (ref "IC2") (pin "3") (pinfunction "~{WP}_3") (pintype "input"))
      (node (ref "JP1") (pin "2") (pinfunction "2_2") (pintype "passive"))
      (node (ref "R47") (pin "1") (pinfunction "1_1") (pintype "passive"))
    )
    (net (code "59") (name "Net-(Q5-B)") (class "Default")
      (node (ref "Q5") (pin "1") (pinfunction "B_1") (pintype "passive"))
      (node (ref "R8") (pin "2") (pinfunction "2_2") (pintype "passive"))
    )
    (net (code "60") (name "Net-(Q5-E)") (class "Default")
      (node (ref "Q5") (pin "2") (pinfunction "E_2") (pintype "passive"))
      (node (ref "R13") (pin "2") (pinfunction "2_2") (pintype "passive"))
      (node (ref "R14") (pin "2") (pinfunction "2_2") (pintype "passive"))
    )
    (net (code "61") (name "Net-(Q6-B)") (class "Default")
      (node (ref "Q6") (pin "1") (pinfunction "B_1") (pintype "passive"))
      (node (ref "R10") (pin "2") (pinfunction "2_2") (pintype "passive"))
      (node (ref "R9") (pin "2") (pinfunction "2_2") (pintype "passive"))
    )
    (net (code "62") (name "Net-(Q6-E)") (class "Default")
      (node (ref "Q6") (pin "2") (pinfunction "E_2") (pintype "passive"))
      (node (ref "R15") (pin "2") (pinfunction "2_2") (pintype "passive"))
      (node (ref "R16") (pin "2") (pinfunction "2_2") (pintype "passive"))
      (node (ref "R20") (pin "2") (pinfunction "2_2") (pintype "passive"))
    )
    (net (code "63") (name "Net-(Q7-B)") (class "Default")
      (node (ref "Q7") (pin "1") (pinfunction "B_1") (pintype "passive"))
      (node (ref "R29") (pin "2") (pinfunction "2_2") (pintype "passive"))
      (node (ref "R30") (pin "2") (pinfunction "2_2") (pintype "passive"))
    )
    (net (code "64") (name "Net-(Q7-E)") (class "Default")
      (node (ref "Q7") (pin "2") (pinfunction "E_2") (pintype "passive"))
      (node (ref "R31") (pin "2") (pinfunction "2_2") (pintype "passive"))
      (node (ref "R32") (pin "2") (pinfunction "2_2") (pintype "passive"))
      (node (ref "R33") (pin "2") (pinfunction "2_2") (pintype "passive"))
    )
    (net (code "65") (name "Net-(Q8-B)") (class "Default")
      (node (ref "Q8") (pin "1") (pinfunction "B_1") (pintype "passive"))
      (node (ref "R24") (pin "2") (pinfunction "2_2") (pintype "passive"))
      (node (ref "R25") (pin "2") (pinfunction "2_2") (pintype "passive"))
    )
    (net (code "66") (name "Net-(Q8-E)") (class "Default")
      (node (ref "Q8") (pin "2") (pinfunction "E_2") (pintype "passive"))
      (node (ref "R26") (pin "2") (pinfunction "2_2") (pintype "passive"))
      (node (ref "R27") (pin "2") (pinfunction "2_2") (pintype "passive"))
      (node (ref "R28") (pin "2") (pinfunction "2_2") (pintype "passive"))
    )
    (net (code "67") (name "Net-(R18-Pad2)") (class "Default")
      (node (ref "R18") (pin "2") (pinfunction "2_2") (pintype "passive"))
      (node (ref "R22") (pin "2") (pinfunction "2_2") (pintype "passive"))
    )
    (net (code "68") (name "Net-(T2-B)") (class "Default")
      (node (ref "C2") (pin "2") (pinfunction "2_2") (pintype "passive"))
      (node (ref "R18") (pin "1") (pinfunction "1_1") (pintype "passive"))
      (node (ref "R19") (pin "2") (pinfunction "2_2") (pintype "passive"))
      (node (ref "T2") (pin "1") (pinfunction "B_1") (pintype "passive"))
    )
    (net (code "69") (name "Net-(U$1-A0)") (class "Default")
      (node (ref "U$1") (pin "P20") (pinfunction "A0_P20") (pintype "bidirectional"))
      (node (ref "U1") (pin "P5") (pinfunction "IO_L20P_7_P5") (pintype "bidirectional"))
    )
    (net (code "70") (name "Net-(U$1-A1)") (class "Default")
      (node (ref "U$1") (pin "P19") (pinfunction "A1_P19") (pintype "bidirectional"))
      (node (ref "U1") (pin "P4") (pinfunction "IOVREF_7_P4") (pintype "bidirectional"))
    )
    (net (code "71") (name "Net-(U$1-A2)") (class "Default")
      (node (ref "U$1") (pin "P18") (pinfunction "A2_P18") (pintype "bidirectional"))
      (node (ref "U1") (pin "P2") (pinfunction "IO_L01N_7VRP_7_P2") (pintype "bidirectional"))
    )
    (net (code "72") (name "Net-(U$1-A3)") (class "Default")
      (node (ref "U$1") (pin "P17") (pinfunction "A3_P17") (pintype "bidirectional"))
      (node (ref "U1") (pin "P1") (pinfunction "IO_L01P_7VRN_7_P1") (pintype "bidirectional"))
    )
    (net (code "73") (name "Net-(U$1-A4)") (class "Default")
      (node (ref "U$1") (pin "P16") (pinfunction "A4_P16") (pintype "bidirectional"))
      (node (ref "U1") (pin "P36") (pinfunction "IO_L01N_6VRP_6_P36") (pintype "bidirectional"))
    )
    (net (code "74") (name "Net-(U$1-A5)") (class "Default")
      (node (ref "U$1") (pin "P15") (pinfunction "A5_P15") (pintype "bidirectional"))
      (node (ref "U1") (pin "P35") (pinfunction "IO_L01P_6VRN_6_P35") (pintype "bidirectional"))
    )
    (net (code "75") (name "Net-(U$1-A6)") (class "Default")
      (node (ref "U$1") (pin "P14") (pinfunction "A6_P14") (pintype "bidirectional"))
      (node (ref "U1") (pin "P33") (pinfunction "IO_L20N_6_P33") (pintype "bidirectional"))
    )
    (net (code "76") (name "Net-(U$1-A7)") (class "Default")
      (node (ref "U$1") (pin "P13") (pinfunction "A7_P13") (pintype "bidirectional"))
      (node (ref "U1") (pin "P32") (pinfunction "IO_L20P_6_P32") (pintype "bidirectional"))
    )
    (net (code "77") (name "Net-(U$1-A8)") (class "Default")
      (node (ref "U$1") (pin "P3") (pinfunction "A8_P3") (pintype "bidirectional"))
      (node (ref "U1") (pin "P21") (pinfunction "IO_L40N_6_P21") (pintype "bidirectional"))
    )
    (net (code "78") (name "Net-(U$1-A9)") (class "Default")
      (node (ref "U$1") (pin "P2") (pinfunction "A9_P2") (pintype "bidirectional"))
      (node (ref "U1") (pin "P20") (pinfunction "IO_L40P_6VREF_6_P20") (pintype "bidirectional"))
    )
    (net (code "79") (name "Net-(U$1-A10)") (class "Default")
      (node (ref "U$1") (pin "P31") (pinfunction "A10_P31") (pintype "bidirectional"))
      (node (ref "U1") (pin "P15") (pinfunction "IO_L24N_7_P15") (pintype "bidirectional"))
    )
    (net (code "80") (name "Net-(U$1-A11)") (class "Default")
      (node (ref "U$1") (pin "P1") (pinfunction "A11_P1") (pintype "bidirectional"))
      (node (ref "U1") (pin "P18") (pinfunction "IO_L40N_7VREF_7_P18") (pintype "bidirectional"))
    )
    (net (code "81") (name "Net-(U$1-A12)") (class "Default")
      (node (ref "U$1") (pin "P12") (pinfunction "A12_P12") (pintype "bidirectional"))
      (node (ref "U1") (pin "P31") (pinfunction "IO_L21N_6_P31") (pintype "bidirectional"))
    )
    (net (code "82") (name "Net-(U$1-A13)") (class "Default")
      (node (ref "U$1") (pin "P4") (pinfunction "A13_P4") (pintype "bidirectional"))
      (node (ref "U1") (pin "P23") (pinfunction "IO_L24P_6_P23") (pintype "bidirectional"))
    )
    (net (code "83") (name "Net-(U$1-A14)") (class "Default")
      (node (ref "U$1") (pin "P11") (pinfunction "A14_P11") (pintype "bidirectional"))
      (node (ref "U1") (pin "P30") (pinfunction "IO_L21P_6_P30") (pintype "bidirectional"))
    )
    (net (code "84") (name "Net-(U$1-A15)") (class "Default")
      (node (ref "U$1") (pin "P7") (pinfunction "A15_P7") (pintype "bidirectional"))
      (node (ref "U1") (pin "P26") (pinfunction "IO_L23N_6_P26") (pintype "bidirectional"))
    )
    (net (code "85") (name "Net-(U$1-A16)") (class "Default")
      (node (ref "U$1") (pin "P10") (pinfunction "A16_P10") (pintype "bidirectional"))
      (node (ref "U1") (pin "P28") (pinfunction "IO_L22N_6_P28") (pintype "bidirectional"))
    )
    (net (code "86") (name "Net-(U$1-A17)") (class "Default")
      (node (ref "U$1") (pin "P6") (pinfunction "A17_P6") (pintype "bidirectional"))
      (node (ref "U1") (pin "P25") (pinfunction "IO_L23P_6_P25") (pintype "bidirectional"))
    )
    (net (code "87") (name "Net-(U$1-A18)") (class "Default")
      (node (ref "U$1") (pin "P9") (pinfunction "A18_P9") (pintype "bidirectional"))
      (node (ref "U1") (pin "P27") (pinfunction "IO_L22P_6_P27") (pintype "bidirectional"))
    )
    (net (code "88") (name "Net-(U$1-DQ0)") (class "Default")
      (node (ref "U$1") (pin "P21") (pinfunction "DQ0_P21") (pintype "bidirectional"))
      (node (ref "U1") (pin "P6") (pinfunction "IO_L20N_7_P6") (pintype "bidirectional"))
    )
    (net (code "89") (name "Net-(U$1-DQ1)") (class "Default")
      (node (ref "U$1") (pin "P22") (pinfunction "DQ1_P22") (pintype "bidirectional"))
      (node (ref "U1") (pin "P7") (pinfunction "IO_L21P_7_P7") (pintype "bidirectional"))
    )
    (net (code "90") (name "Net-(U$1-DQ2)") (class "Default")
      (node (ref "U$1") (pin "P23") (pinfunction "DQ2_P23") (pintype "bidirectional"))
      (node (ref "U1") (pin "P8") (pinfunction "IO_L21N_7_P8") (pintype "bidirectional"))
    )
    (net (code "91") (name "Net-(U$1-DQ3)") (class "Default")
      (node (ref "U$1") (pin "P25") (pinfunction "DQ3_P25") (pintype "bidirectional"))
      (node (ref "U1") (pin "P10") (pinfunction "IO_L22P_7_P10") (pintype "bidirectional"))
    )
    (net (code "92") (name "Net-(U$1-DQ4)") (class "Default")
      (node (ref "U$1") (pin "P26") (pinfunction "DQ4_P26") (pintype "bidirectional"))
      (node (ref "U1") (pin "P11") (pinfunction "IO_L22N_7_P11") (pintype "bidirectional"))
    )
    (net (code "93") (name "Net-(U$1-DQ5)") (class "Default")
      (node (ref "U$1") (pin "P27") (pinfunction "DQ5_P27") (pintype "bidirectional"))
      (node (ref "U1") (pin "P12") (pinfunction "IO_L23P_7_P12") (pintype "bidirectional"))
    )
    (net (code "94") (name "Net-(U$1-DQ6)") (class "Default")
      (node (ref "U$1") (pin "P28") (pinfunction "DQ6_P28") (pintype "bidirectional"))
      (node (ref "U1") (pin "P13") (pinfunction "IO_L23N_7_P13") (pintype "bidirectional"))
    )
    (net (code "95") (name "Net-(U$1-DQ7)") (class "Default")
      (node (ref "U$1") (pin "P29") (pinfunction "DQ7_P29") (pintype "bidirectional"))
      (node (ref "U1") (pin "P14") (pinfunction "IO_L24P_7_P14") (pintype "bidirectional"))
    )
    (net (code "96") (name "Net-(U$1-OE)") (class "Default")
      (node (ref "U$1") (pin "P32") (pinfunction "OE_P32") (pintype "bidirectional"))
      (node (ref "U1") (pin "P17") (pinfunction "IO_L40P_7_P17") (pintype "bidirectional"))
    )
    (net (code "97") (name "Net-(U$1-WE)") (class "Default")
      (node (ref "U$1") (pin "P5") (pinfunction "WE_P5") (pintype "bidirectional"))
      (node (ref "U1") (pin "P24") (pinfunction "IO_L24N_6VREF_6_P24") (pintype "bidirectional"))
    )
    (net (code "98") (name "Net-(U1I-IO_L32P_5GCLK2)") (class "Default")
      (node (ref "U$2") (pin "OUT") (pinfunction "OUT_OUT") (pintype "output"))
      (node (ref "U1") (pin "P52") (pinfunction "IO_L32P_5GCLK2_P52") (pintype "bidirectional"))
    )
    (net (code "99") (name "Net-(U1N-TCK)") (class "Default")
      (node (ref "R2") (pin "1") (pinfunction "1_1") (pintype "passive"))
      (node (ref "U1") (pin "P110") (pinfunction "TCK_P110") (pintype "bidirectional"))
    )
    (net (code "100") (name "Net-(U1N-TDI)") (class "Default")
      (node (ref "R1") (pin "1") (pinfunction "1_1") (pintype "passive"))
      (node (ref "U1") (pin "P144") (pinfunction "TDI_P144") (pintype "bidirectional"))
    )
    (net (code "101") (name "Net-(U1N-TMS)") (class "Default")
      (node (ref "R3") (pin "1") (pinfunction "1_1") (pintype "passive"))
      (node (ref "U1") (pin "P111") (pinfunction "TMS_P111") (pintype "bidirectional"))
    )
    (net (code "102") (name "Net-(X4A-F)") (class "Default")
      (node (ref "R40") (pin "2") (pinfunction "2_2") (pintype "passive"))
      (node (ref "X4") (pin "1") (pinfunction "F_1") (pintype "passive"))
    )
    (net (code "103") (name "Net-(X4B-F)") (class "Default")
      (node (ref "R41") (pin "2") (pinfunction "2_2") (pintype "passive"))
      (node (ref "X4") (pin "2") (pinfunction "F_2") (pintype "passive"))
    )
    (net (code "104") (name "Net-(X4C-F)") (class "Default")
      (node (ref "R42") (pin "2") (pinfunction "2_2") (pintype "passive"))
      (node (ref "X4") (pin "3") (pinfunction "F_3") (pintype "passive"))
    )
    (net (code "105") (name "Net-(X4D-F)") (class "Default")
      (node (ref "R43") (pin "2") (pinfunction "2_2") (pintype "passive"))
      (node (ref "X4") (pin "4") (pinfunction "F_4") (pintype "passive"))
    )
    (net (code "106") (name "Net-(X4F-F)") (class "Default")
      (node (ref "R44") (pin "2") (pinfunction "2_2") (pintype "passive"))
      (node (ref "X4") (pin "6") (pinfunction "F_6") (pintype "passive"))
    )
    (net (code "107") (name "Net-(X4G-F)") (class "Default")
      (node (ref "R45") (pin "2") (pinfunction "2_2") (pintype "passive"))
      (node (ref "X4") (pin "7") (pinfunction "F_7") (pintype "passive"))
    )
    (net (code "108") (name "Net-(X5A-F)") (class "Default")
      (node (ref "R46") (pin "1") (pinfunction "1_1") (pintype "passive"))
      (node (ref "X5") (pin "1") (pinfunction "F_1") (pintype "passive"))
    )
    (net (code "109") (name "Net-(X5B-F)") (class "Default")
      (node (ref "R39") (pin "1") (pinfunction "1_1") (pintype "passive"))
      (node (ref "X5") (pin "2") (pinfunction "F_2") (pintype "passive"))
    )
    (net (code "110") (name "Net-(X5C-F)") (class "Default")
      (node (ref "R38") (pin "1") (pinfunction "1_1") (pintype "passive"))
      (node (ref "X5") (pin "3") (pinfunction "F_3") (pintype "passive"))
    )
    (net (code "111") (name "Net-(X5D-F)") (class "Default")
      (node (ref "R37") (pin "1") (pinfunction "1_1") (pintype "passive"))
      (node (ref "X5") (pin "4") (pinfunction "F_4") (pintype "passive"))
    )
    (net (code "112") (name "Net-(X5F-F)") (class "Default")
      (node (ref "R36") (pin "1") (pinfunction "1_1") (pintype "passive"))
      (node (ref "X5") (pin "6") (pinfunction "F_6") (pintype "passive"))
    )
    (net (code "113") (name "Net-(X5G-F)") (class "Default")
      (node (ref "R35") (pin "1") (pinfunction "1_1") (pintype "passive"))
      (node (ref "X5") (pin "7") (pinfunction "F_7") (pintype "passive"))
    )
    (net (code "114") (name "unconnected-(IC1-NC.1-Pad2)") (class "Default")
      (node (ref "IC1") (pin "2") (pinfunction "NC.1_2") (pintype "bidirectional"))
    )
    (net (code "115") (name "unconnected-(IC1-NC.2-Pad9)") (class "Default")
      (node (ref "IC1") (pin "9") (pinfunction "NC.2_9") (pintype "bidirectional"))
    )
    (net (code "116") (name "unconnected-(IC1-NC.3-Pad12)") (class "Default")
      (node (ref "IC1") (pin "12") (pinfunction "NC.3_12") (pintype "bidirectional"))
    )
    (net (code "117") (name "unconnected-(IC1-NC.4-Pad14)") (class "Default")
      (node (ref "IC1") (pin "14") (pinfunction "NC.4_14") (pintype "bidirectional"))
    )
    (net (code "118") (name "unconnected-(IC1-NC.5-Pad15)") (class "Default")
      (node (ref "IC1") (pin "15") (pinfunction "NC.5_15") (pintype "bidirectional"))
    )
    (net (code "119") (name "unconnected-(IC1-NC.6-Pad16)") (class "Default")
      (node (ref "IC1") (pin "16") (pinfunction "NC.6_16") (pintype "bidirectional"))
    )
    (net (code "120") (name "unconnected-(IC1-{slash}CEO-Pad13)") (class "Default")
      (node (ref "IC1") (pin "13") (pinfunction "/CEO_13") (pintype "bidirectional"))
    )
    (net (code "121") (name "unconnected-(REG1.2-VOUT2-Pad2)") (class "Default")
      (node (ref "REG1.2") (pin "2") (pinfunction "VOUT2_2") (pintype "bidirectional"))
    )
    (net (code "122") (name "unconnected-(REG2.5-VOUT2-Pad2)") (class "Default")
      (node (ref "REG2.5") (pin "2") (pinfunction "VOUT2_2") (pintype "bidirectional"))
    )
    (net (code "123") (name "unconnected-(U$2-TRI-PadENA)") (class "Default")
      (node (ref "U$2") (pin "ENA") (pinfunction "TRI_ENA") (pintype "input"))
    )
    (net (code "124") (name "unconnected-(U1A-IO_L27P_0-PadP135)") (class "Default")
      (node (ref "U1") (pin "P135") (pinfunction "IO_L27P_0_P135") (pintype "bidirectional"))
    )
    (net (code "125") (name "unconnected-(U1A-IO_L30N_0-PadP132)") (class "Default")
      (node (ref "U1") (pin "P132") (pinfunction "IO_L30N_0_P132") (pintype "bidirectional"))
    )
    (net (code "126") (name "unconnected-(U1A-IO_L30P_0-PadP131)") (class "Default")
      (node (ref "U1") (pin "P131") (pinfunction "IO_L30P_0_P131") (pintype "bidirectional"))
    )
    (net (code "127") (name "unconnected-(U1A-IO_L31N_0-PadP130)") (class "Default")
      (node (ref "U1") (pin "P130") (pinfunction "IO_L31N_0_P130") (pintype "bidirectional"))
    )
    (net (code "128") (name "unconnected-(U1A-IO_L31P_0VREF_0-PadP129)") (class "Default")
      (node (ref "U1") (pin "P129") (pinfunction "IO_L31P_0VREF_0_P129") (pintype "bidirectional"))
    )
    (net (code "129") (name "unconnected-(U1A-IO_L32N_0GCLK7-PadP128)") (class "Default")
      (node (ref "U1") (pin "P128") (pinfunction "IO_L32N_0GCLK7_P128") (pintype "bidirectional"))
    )
    (net (code "130") (name "unconnected-(U1A-IO_L32P_0GCLK6-PadP127)") (class "Default")
      (node (ref "U1") (pin "P127") (pinfunction "IO_L32P_0GCLK6_P127") (pintype "bidirectional"))
    )
    (net (code "131") (name "unconnected-(U1C-IO-PadP116)") (class "Default")
      (node (ref "U1") (pin "P116") (pinfunction "IO_P116") (pintype "bidirectional"))
    )
    (net (code "132") (name "unconnected-(U1C-IO_L01N_1VRP_1-PadP113)") (class "Default")
      (node (ref "U1") (pin "P113") (pinfunction "IO_L01N_1VRP_1_P113") (pintype "bidirectional"))
    )
    (net (code "133") (name "unconnected-(U1C-IO_L01P_1VRN_1-PadP112)") (class "Default")
      (node (ref "U1") (pin "P112") (pinfunction "IO_L01P_1VRN_1_P112") (pintype "bidirectional"))
    )
    (net (code "134") (name "unconnected-(U1C-IO_L28N_1-PadP119)") (class "Default")
      (node (ref "U1") (pin "P119") (pinfunction "IO_L28N_1_P119") (pintype "bidirectional"))
    )
    (net (code "135") (name "unconnected-(U1C-IO_L28P_1-PadP118)") (class "Default")
      (node (ref "U1") (pin "P118") (pinfunction "IO_L28P_1_P118") (pintype "bidirectional"))
    )
    (net (code "136") (name "unconnected-(U1C-IO_L31N_1VREF_1-PadP123)") (class "Default")
      (node (ref "U1") (pin "P123") (pinfunction "IO_L31N_1VREF_1_P123") (pintype "bidirectional"))
    )
    (net (code "137") (name "unconnected-(U1C-IO_L31P_1-PadP122)") (class "Default")
      (node (ref "U1") (pin "P122") (pinfunction "IO_L31P_1_P122") (pintype "bidirectional"))
    )
    (net (code "138") (name "unconnected-(U1C-IO_L32N_1GCLK5-PadP125)") (class "Default")
      (node (ref "U1") (pin "P125") (pinfunction "IO_L32N_1GCLK5_P125") (pintype "bidirectional"))
    )
    (net (code "139") (name "unconnected-(U1C-IO_L32P_1GCLK4-PadP124)") (class "Default")
      (node (ref "U1") (pin "P124") (pinfunction "IO_L32P_1GCLK4_P124") (pintype "bidirectional"))
    )
    (net (code "140") (name "unconnected-(U1D-IO_L01N_2VRP_2-PadP108)") (class "Default")
      (node (ref "U1") (pin "P108") (pinfunction "IO_L01N_2VRP_2_P108") (pintype "bidirectional"))
    )
    (net (code "141") (name "unconnected-(U1D-IO_L01P_2VRN_2-PadP107)") (class "Default")
      (node (ref "U1") (pin "P107") (pinfunction "IO_L01P_2VRN_2_P107") (pintype "bidirectional"))
    )
    (net (code "142") (name "unconnected-(U1D-IO_L20N_2-PadP105)") (class "Default")
      (node (ref "U1") (pin "P105") (pinfunction "IO_L20N_2_P105") (pintype "bidirectional"))
    )
    (net (code "143") (name "unconnected-(U1D-IO_L20P_2-PadP104)") (class "Default")
      (node (ref "U1") (pin "P104") (pinfunction "IO_L20P_2_P104") (pintype "bidirectional"))
    )
    (net (code "144") (name "unconnected-(U1D-IO_L21N_2-PadP103)") (class "Default")
      (node (ref "U1") (pin "P103") (pinfunction "IO_L21N_2_P103") (pintype "bidirectional"))
    )
    (net (code "145") (name "unconnected-(U1D-IO_L21P_2-PadP102)") (class "Default")
      (node (ref "U1") (pin "P102") (pinfunction "IO_L21P_2_P102") (pintype "bidirectional"))
    )
    (net (code "146") (name "unconnected-(U1D-IO_L22N_2-PadP100)") (class "Default")
      (node (ref "U1") (pin "P100") (pinfunction "IO_L22N_2_P100") (pintype "bidirectional"))
    )
    (net (code "147") (name "unconnected-(U1D-IO_L22P_2-PadP99)") (class "Default")
      (node (ref "U1") (pin "P99") (pinfunction "IO_L22P_2_P99") (pintype "bidirectional"))
    )
    (net (code "148") (name "unconnected-(U1D-IO_L23N_2VREF_2-PadP98)") (class "Default")
      (node (ref "U1") (pin "P98") (pinfunction "IO_L23N_2VREF_2_P98") (pintype "bidirectional"))
    )
    (net (code "149") (name "unconnected-(U1D-IO_L23P_2-PadP97)") (class "Default")
      (node (ref "U1") (pin "P97") (pinfunction "IO_L23P_2_P97") (pintype "bidirectional"))
    )
    (net (code "150") (name "unconnected-(U1D-IO_L24N_2-PadP96)") (class "Default")
      (node (ref "U1") (pin "P96") (pinfunction "IO_L24N_2_P96") (pintype "bidirectional"))
    )
    (net (code "151") (name "unconnected-(U1D-IO_L24P_2-PadP95)") (class "Default")
      (node (ref "U1") (pin "P95") (pinfunction "IO_L24P_2_P95") (pintype "bidirectional"))
    )
    (net (code "152") (name "unconnected-(U1D-IO_L40N_2-PadP93)") (class "Default")
      (node (ref "U1") (pin "P93") (pinfunction "IO_L40N_2_P93") (pintype "bidirectional"))
    )
    (net (code "153") (name "unconnected-(U1D-IO_L40P_2VREF_2-PadP92)") (class "Default")
      (node (ref "U1") (pin "P92") (pinfunction "IO_L40P_2VREF_2_P92") (pintype "bidirectional"))
    )
    (net (code "154") (name "unconnected-(U1F-IO-PadP76)") (class "Default")
      (node (ref "U1") (pin "P76") (pinfunction "IO_P76") (pintype "bidirectional"))
    )
    (net (code "155") (name "unconnected-(U1F-IO_L01N_3VRP_3-PadP74)") (class "Default")
      (node (ref "U1") (pin "P74") (pinfunction "IO_L01N_3VRP_3_P74") (pintype "bidirectional"))
    )
    (net (code "156") (name "unconnected-(U1F-IO_L01P_3VRN_3-PadP73)") (class "Default")
      (node (ref "U1") (pin "P73") (pinfunction "IO_L01P_3VRN_3_P73") (pintype "bidirectional"))
    )
    (net (code "157") (name "unconnected-(U1F-IO_L20N_3-PadP78)") (class "Default")
      (node (ref "U1") (pin "P78") (pinfunction "IO_L20N_3_P78") (pintype "bidirectional"))
    )
    (net (code "158") (name "unconnected-(U1F-IO_L20P_3-PadP77)") (class "Default")
      (node (ref "U1") (pin "P77") (pinfunction "IO_L20P_3_P77") (pintype "bidirectional"))
    )
    (net (code "159") (name "unconnected-(U1F-IO_L21N_3-PadP80)") (class "Default")
      (node (ref "U1") (pin "P80") (pinfunction "IO_L21N_3_P80") (pintype "bidirectional"))
    )
    (net (code "160") (name "unconnected-(U1F-IO_L21P_3-PadP79)") (class "Default")
      (node (ref "U1") (pin "P79") (pinfunction "IO_L21P_3_P79") (pintype "bidirectional"))
    )
    (net (code "161") (name "unconnected-(U1F-IO_L22N_3-PadP83)") (class "Default")
      (node (ref "U1") (pin "P83") (pinfunction "IO_L22N_3_P83") (pintype "bidirectional"))
    )
    (net (code "162") (name "unconnected-(U1F-IO_L22P_3-PadP82)") (class "Default")
      (node (ref "U1") (pin "P82") (pinfunction "IO_L22P_3_P82") (pintype "bidirectional"))
    )
    (net (code "163") (name "unconnected-(U1F-IO_L23N_3-PadP85)") (class "Default")
      (node (ref "U1") (pin "P85") (pinfunction "IO_L23N_3_P85") (pintype "bidirectional"))
    )
    (net (code "164") (name "unconnected-(U1F-IO_L23P_3VREF_3-PadP84)") (class "Default")
      (node (ref "U1") (pin "P84") (pinfunction "IO_L23P_3VREF_3_P84") (pintype "bidirectional"))
    )
    (net (code "165") (name "unconnected-(U1F-IO_L24N_3-PadP87)") (class "Default")
      (node (ref "U1") (pin "P87") (pinfunction "IO_L24N_3_P87") (pintype "bidirectional"))
    )
    (net (code "166") (name "unconnected-(U1F-IO_L24P_3-PadP86)") (class "Default")
      (node (ref "U1") (pin "P86") (pinfunction "IO_L24P_3_P86") (pintype "bidirectional"))
    )
    (net (code "167") (name "unconnected-(U1F-IO_L40N_3VREF_3-PadP90)") (class "Default")
      (node (ref "U1") (pin "P90") (pinfunction "IO_L40N_3VREF_3_P90") (pintype "bidirectional"))
    )
    (net (code "168") (name "unconnected-(U1F-IO_L40P_3-PadP89)") (class "Default")
      (node (ref "U1") (pin "P89") (pinfunction "IO_L40P_3_P89") (pintype "bidirectional"))
    )
    (net (code "169") (name "unconnected-(U1G-IOVREF_4-PadP70)") (class "Default")
      (node (ref "U1") (pin "P70") (pinfunction "IOVREF_4_P70") (pintype "bidirectional"))
    )
    (net (code "170") (name "unconnected-(U1G-IO_L01N_4VRP_4-PadP69)") (class "Default")
      (node (ref "U1") (pin "P69") (pinfunction "IO_L01N_4VRP_4_P69") (pintype "bidirectional"))
    )
    (net (code "171") (name "unconnected-(U1G-IO_L01P_4VRN_4-PadP68)") (class "Default")
      (node (ref "U1") (pin "P68") (pinfunction "IO_L01P_4VRN_4_P68") (pintype "bidirectional"))
    )
    (net (code "172") (name "unconnected-(U1G-IO_L27P_4D1-PadP63)") (class "Default")
      (node (ref "U1") (pin "P63") (pinfunction "IO_L27P_4D1_P63") (pintype "bidirectional"))
    )
    (net (code "173") (name "unconnected-(U1G-IO_L30N_4D2-PadP60)") (class "Default")
      (node (ref "U1") (pin "P60") (pinfunction "IO_L30N_4D2_P60") (pintype "bidirectional"))
    )
    (net (code "174") (name "unconnected-(U1G-IO_L30P_4D3-PadP59)") (class "Default")
      (node (ref "U1") (pin "P59") (pinfunction "IO_L30P_4D3_P59") (pintype "bidirectional"))
    )
    (net (code "175") (name "unconnected-(U1G-IO_L31P_4DOUTBUSY-PadP57)") (class "Default")
      (node (ref "U1") (pin "P57") (pinfunction "IO_L31P_4DOUTBUSY_P57") (pintype "bidirectional"))
    )
    (net (code "176") (name "unconnected-(U1G-IO_L32N_4GCLK1-PadP56)") (class "Default")
      (node (ref "U1") (pin "P56") (pinfunction "IO_L32N_4GCLK1_P56") (pintype "bidirectional"))
    )
    (net (code "177") (name "unconnected-(U1G-IO_L32P_4GCLK0-PadP55)") (class "Default")
      (node (ref "U1") (pin "P55") (pinfunction "IO_L32P_4GCLK0_P55") (pintype "bidirectional"))
    )
    (net (code "178") (name "unconnected-(U1I-IO_L31N_5D4-PadP51)") (class "Default")
      (node (ref "U1") (pin "P51") (pinfunction "IO_L31N_5D4_P51") (pintype "bidirectional"))
    )
    (net (code "179") (name "unconnected-(U1I-IO_L32N_5GCLK3-PadP53)") (class "Default")
      (node (ref "U1") (pin "P53") (pinfunction "IO_L32N_5GCLK3_P53") (pintype "bidirectional"))
    )
    (net (code "180") (name "unconnected-(U1N-HSWAP_EN-PadP142)") (class "Default")
      (node (ref "U1") (pin "P142") (pinfunction "HSWAP_EN_P142") (pintype "bidirectional"))
    )
    (net (code "181") (name "unconnected-(X1-3-Pad2)") (class "Default")
      (node (ref "X1") (pin "2") (pinfunction "3_2") (pintype "passive"))
    )
    (net (code "182") (name "unconnected-(X2-Pad10)") (class "Default")
      (node (ref "X2") (pin "10") (pinfunction "10_10") (pintype "passive"))
    )
    (net (code "183") (name "unconnected-(X2-Pad12)") (class "Default")
      (node (ref "X2") (pin "12") (pinfunction "12_12") (pintype "passive"))
    )
    (net (code "184") (name "unconnected-(X3-Pad2)") (class "Default")
      (node (ref "X3") (pin "2") (pinfunction "2_2") (pintype "passive"))
    )
    (net (code "185") (name "unconnected-(X3-Pad8)") (class "Default")
      (node (ref "X3") (pin "8") (pinfunction "8_8") (pintype "passive"))
    )
    (net (code "186") (name "unconnected-(X4-PadG2)") (class "Default")
      (node (ref "X4") (pin "G2") (pinfunction "G2_G2") (pintype "passive"))
    )
    (net (code "187") (name "unconnected-(X5-PadG2)") (class "Default")
      (node (ref "X5") (pin "G2") (pinfunction "G2_G2") (pintype "passive"))
    )
  )
)
